# Power.net
KiCad netlist of a schematic drawn in Altium Designer
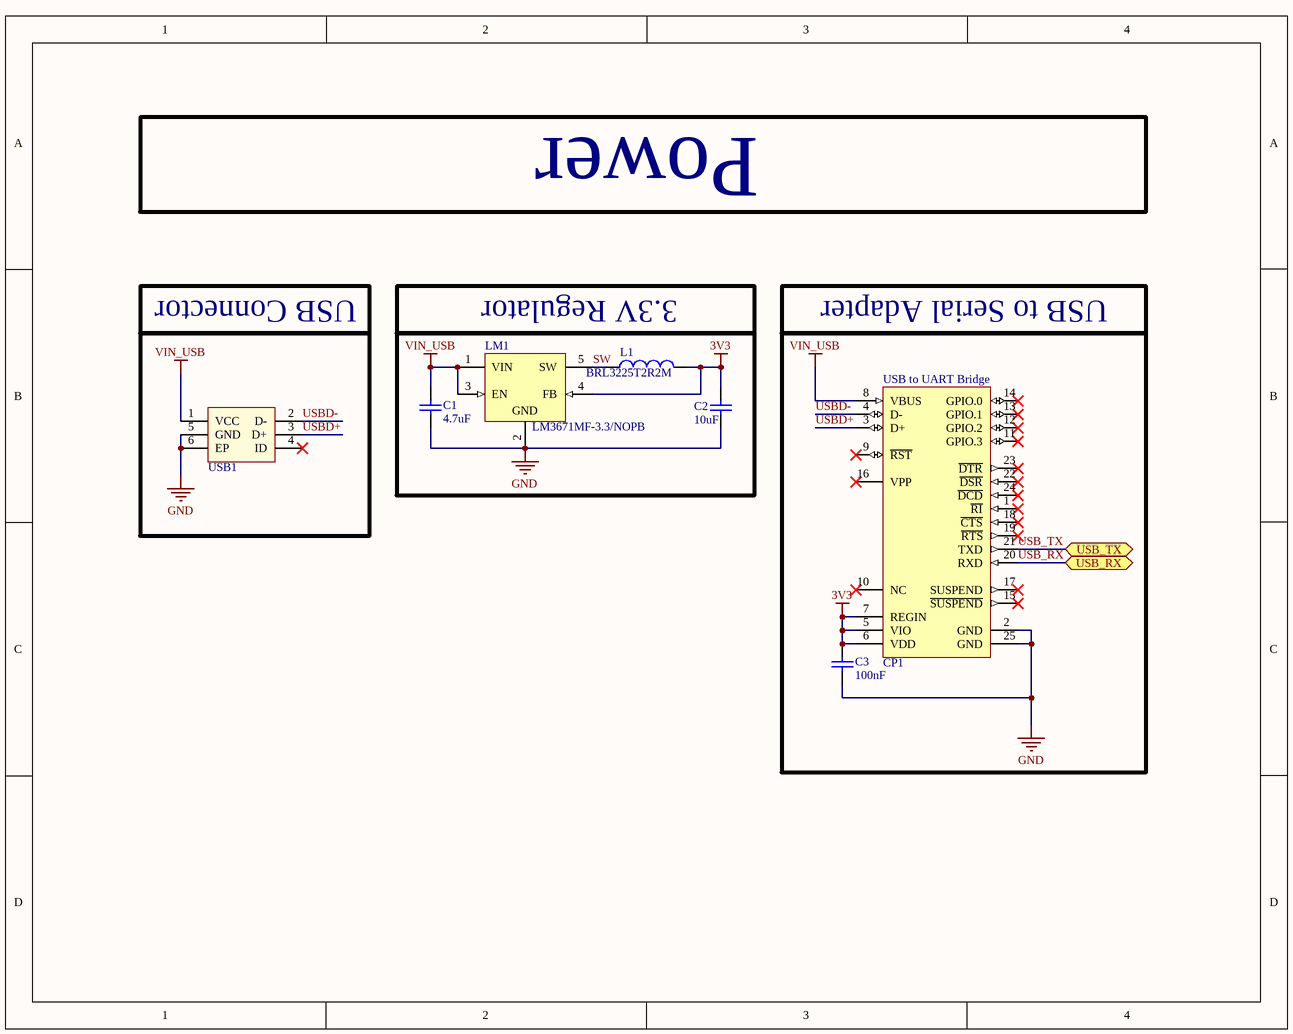
[diagram p0: Power.SchDoc]

(export (version "E")
  (design (tool "Eeschema 10.0.6"))
  (components
    (comp (ref "C1")
      (value "4.7uF")
      (footprint "CAPC0805(2012)145_L")
      (description "CAP 4.7uF 10V ±20% 0805 (2012 Metric) Thickness 1.45mm SMD")
      (fields (field (name "TOLERANCE") "Â±20%"))
      (libsource (lib "Altium Content Vault") (part "CMP-1036-04884-1"))
    )
    (comp (ref "C2")
      (value "10uF")
      (footprint "CAPC0805(2012)100_L")
      (description "CAP 10uF 10V ±20% 0805 (2012 Metric) Thickness 1mm SMD")
      (fields (field (name "TOLERANCE") "Â±20%"))
      (libsource (lib "Altium Content Vault") (part "CMP-1036-04925-1"))
    )
    (comp (ref "C3")
      (value "100nF")
      (footprint "CAPC0805(2012)100_L")
      (description "CAP 100nF 10V ±10% 0805 (2012 Metric) Thickness 1mm SMD")
      (fields (field (name "TOLERANCE") "Â±10%"))
      (libsource (lib "Altium Content Vault") (part "CMP-1036-04394-1"))
    )
    (comp (ref "CP1")
      (value "USB to UART Bridge")
      (footprint "PCBComponent")
      (description "USB to UART bridge")
      (libsource (lib "BG Vault") (part "CP2104-A.2"))
    )
    (comp (ref "L1")
      (value "BRL3225T2R2M")
      (footprint "C1210_L")
      (description "INDUCTOR 2.2UH 1.85A 20% 1210 SM")
      (fields (field (name "TOLERANCE") "±20%") (field (name "MANUFACTURER") "Taiyo Yuden"))
      (libsource (lib "BG Vault") (part "IND-BRL3225T2R2M-2"))
    )
    (comp (ref "LM1")
      (value "LM3671MF-3.3/NOPB")
      (footprint "DBV0005A_N")
      (description "2MHz, 600mA Step-Down DC-DC Converter, 5-pin SOT-23, Pb-Free")
      (fields (field (name "MANUFACTURER") "Texas Instruments"))
      (libsource (lib "Altium Content Vault") (part "CMP-0063-01132-3"))
    )
    (comp (ref "USB1")
      (value "USB3100-30-A Flipped USB")
      (footprint "PCBComponent")
      (libsource (lib "BG Vault") (part "USB3100-30-A-A.1"))
    )
  )
  (nets
    (net (code "1") (name "/SW") (class "Default")
      (node (ref "L1") (pin "1") (pinfunction "1_1") (pintype "passive"))
      (node (ref "LM1") (pin "5") (pinfunction "SW_5") (pintype "power_in"))
    )
    (net (code "2") (name "/USBD+") (class "Default")
      (node (ref "CP1") (pin "3") (pinfunction "D+_3") (pintype "bidirectional"))
      (node (ref "USB1") (pin "3") (pinfunction "D+_3") (pintype "passive"))
    )
    (net (code "3") (name "/USBD-") (class "Default")
      (node (ref "CP1") (pin "4") (pinfunction "D-_4") (pintype "bidirectional"))
      (node (ref "USB1") (pin "2") (pinfunction "D-_2") (pintype "passive"))
    )
    (net (code "4") (name "/USB_RX") (class "Default")
      (node (ref "CP1") (pin "20") (pinfunction "RXD_20") (pintype "input"))
    )
    (net (code "5") (name "/USB_TX") (class "Default")
      (node (ref "CP1") (pin "21") (pinfunction "TXD_21") (pintype "output"))
    )
    (net (code "6") (name "3V3") (class "Default")
      (node (ref "C2") (pin "2") (pinfunction "2_2") (pintype "passive"))
      (node (ref "C3") (pin "2") (pinfunction "2_2") (pintype "passive"))
      (node (ref "CP1") (pin "5") (pinfunction "VIO_5") (pintype "power_in"))
      (node (ref "CP1") (pin "6") (pinfunction "VDD_6") (pintype "power_in"))
      (node (ref "CP1") (pin "7") (pinfunction "REGIN_7") (pintype "power_in"))
      (node (ref "L1") (pin "2") (pinfunction "2_2") (pintype "passive"))
      (node (ref "LM1") (pin "4") (pinfunction "FB_4") (pintype "input"))
    )
    (net (code "7") (name "GND") (class "Default")
      (node (ref "C1") (pin "1") (pinfunction "1_1") (pintype "passive"))
      (node (ref "C2") (pin "1") (pinfunction "1_1") (pintype "passive"))
      (node (ref "C3") (pin "1") (pinfunction "1_1") (pintype "passive"))
      (node (ref "CP1") (pin "2") (pinfunction "GND_2") (pintype "power_in"))
      (node (ref "CP1") (pin "25") (pinfunction "GND_25") (pintype "power_in"))
      (node (ref "LM1") (pin "2") (pinfunction "GND_2") (pintype "power_in"))
      (node (ref "USB1") (pin "5") (pinfunction "GND_5") (pintype "passive"))
      (node (ref "USB1") (pin "6") (pinfunction "EP_6") (pintype "passive"))
    )
    (net (code "8") (name "VIN_USB") (class "Default")
      (node (ref "C1") (pin "2") (pinfunction "2_2") (pintype "passive"))
      (node (ref "CP1") (pin "8") (pinfunction "VBUS_8") (pintype "input"))
      (node (ref "LM1") (pin "1") (pinfunction "VIN_1") (pintype "power_in"))
      (node (ref "LM1") (pin "3") (pinfunction "EN_3") (pintype "input"))
      (node (ref "USB1") (pin "1") (pinfunction "VCC_1") (pintype "passive"))
    )
    (net (code "9") (name "unconnected-(CP1-GPIO.0-Pad14)") (class "Default")
      (node (ref "CP1") (pin "14") (pinfunction "GPIO.0_14") (pintype "bidirectional+no_connect"))
    )
    (net (code "10") (name "unconnected-(CP1-GPIO.1-Pad13)") (class "Default")
      (node (ref "CP1") (pin "13") (pinfunction "GPIO.1_13") (pintype "bidirectional+no_connect"))
    )
    (net (code "11") (name "unconnected-(CP1-GPIO.2-Pad12)") (class "Default")
      (node (ref "CP1") (pin "12") (pinfunction "GPIO.2_12") (pintype "bidirectional+no_connect"))
    )
    (net (code "12") (name "unconnected-(CP1-GPIO.3-Pad11)") (class "Default")
      (node (ref "CP1") (pin "11") (pinfunction "GPIO.3_11") (pintype "bidirectional+no_connect"))
    )
    (net (code "13") (name "unconnected-(CP1-NC-Pad10)") (class "Default")
      (node (ref "CP1") (pin "10") (pinfunction "NC_10") (pintype "passive+no_connect"))
    )
    (net (code "14") (name "unconnected-(CP1-SUSPEND-Pad17)") (class "Default")
      (node (ref "CP1") (pin "17") (pinfunction "SUSPEND_17") (pintype "output+no_connect"))
    )
    (net (code "15") (name "unconnected-(CP1-VPP-Pad16)") (class "Default")
      (node (ref "CP1") (pin "16") (pinfunction "VPP_16") (pintype "passive+no_connect"))
    )
    (net (code "16") (name "unconnected-(CP1-~{CTS}-Pad18)") (class "Default")
      (node (ref "CP1") (pin "18") (pinfunction "~{CTS}_18") (pintype "input+no_connect"))
    )
    (net (code "17") (name "unconnected-(CP1-~{DCD}-Pad24)") (class "Default")
      (node (ref "CP1") (pin "24") (pinfunction "~{DCD}_24") (pintype "input+no_connect"))
    )
    (net (code "18") (name "unconnected-(CP1-~{DSR}-Pad22)") (class "Default")
      (node (ref "CP1") (pin "22") (pinfunction "~{DSR}_22") (pintype "input+no_connect"))
    )
    (net (code "19") (name "unconnected-(CP1-~{DTR}-Pad23)") (class "Default")
      (node (ref "CP1") (pin "23") (pinfunction "~{DTR}_23") (pintype "output+no_connect"))
    )
    (net (code "20") (name "unconnected-(CP1-~{RI}-Pad1)") (class "Default")
      (node (ref "CP1") (pin "1") (pinfunction "~{RI}_1") (pintype "input+no_connect"))
    )
    (net (code "21") (name "unconnected-(CP1-~{RST}-Pad9)") (class "Default")
      (node (ref "CP1") (pin "9") (pinfunction "~{RST}_9") (pintype "bidirectional+no_connect"))
    )
    (net (code "22") (name "unconnected-(CP1-~{RTS}-Pad19)") (class "Default")
      (node (ref "CP1") (pin "19") (pinfunction "~{RTS}_19") (pintype "output+no_connect"))
    )
    (net (code "23") (name "unconnected-(CP1-~{SUSPEND}-Pad15)") (class "Default")
      (node (ref "CP1") (pin "15") (pinfunction "~{SUSPEND}_15") (pintype "output+no_connect"))
    )
    (net (code "24") (name "unconnected-(USB1-ID-Pad4)") (class "Default")
      (node (ref "USB1") (pin "4") (pinfunction "ID_4") (pintype "passive+no_connect"))
    )
  )
)
